# circuit.net
KiCad netlist of a schematic drawn in EAGLE
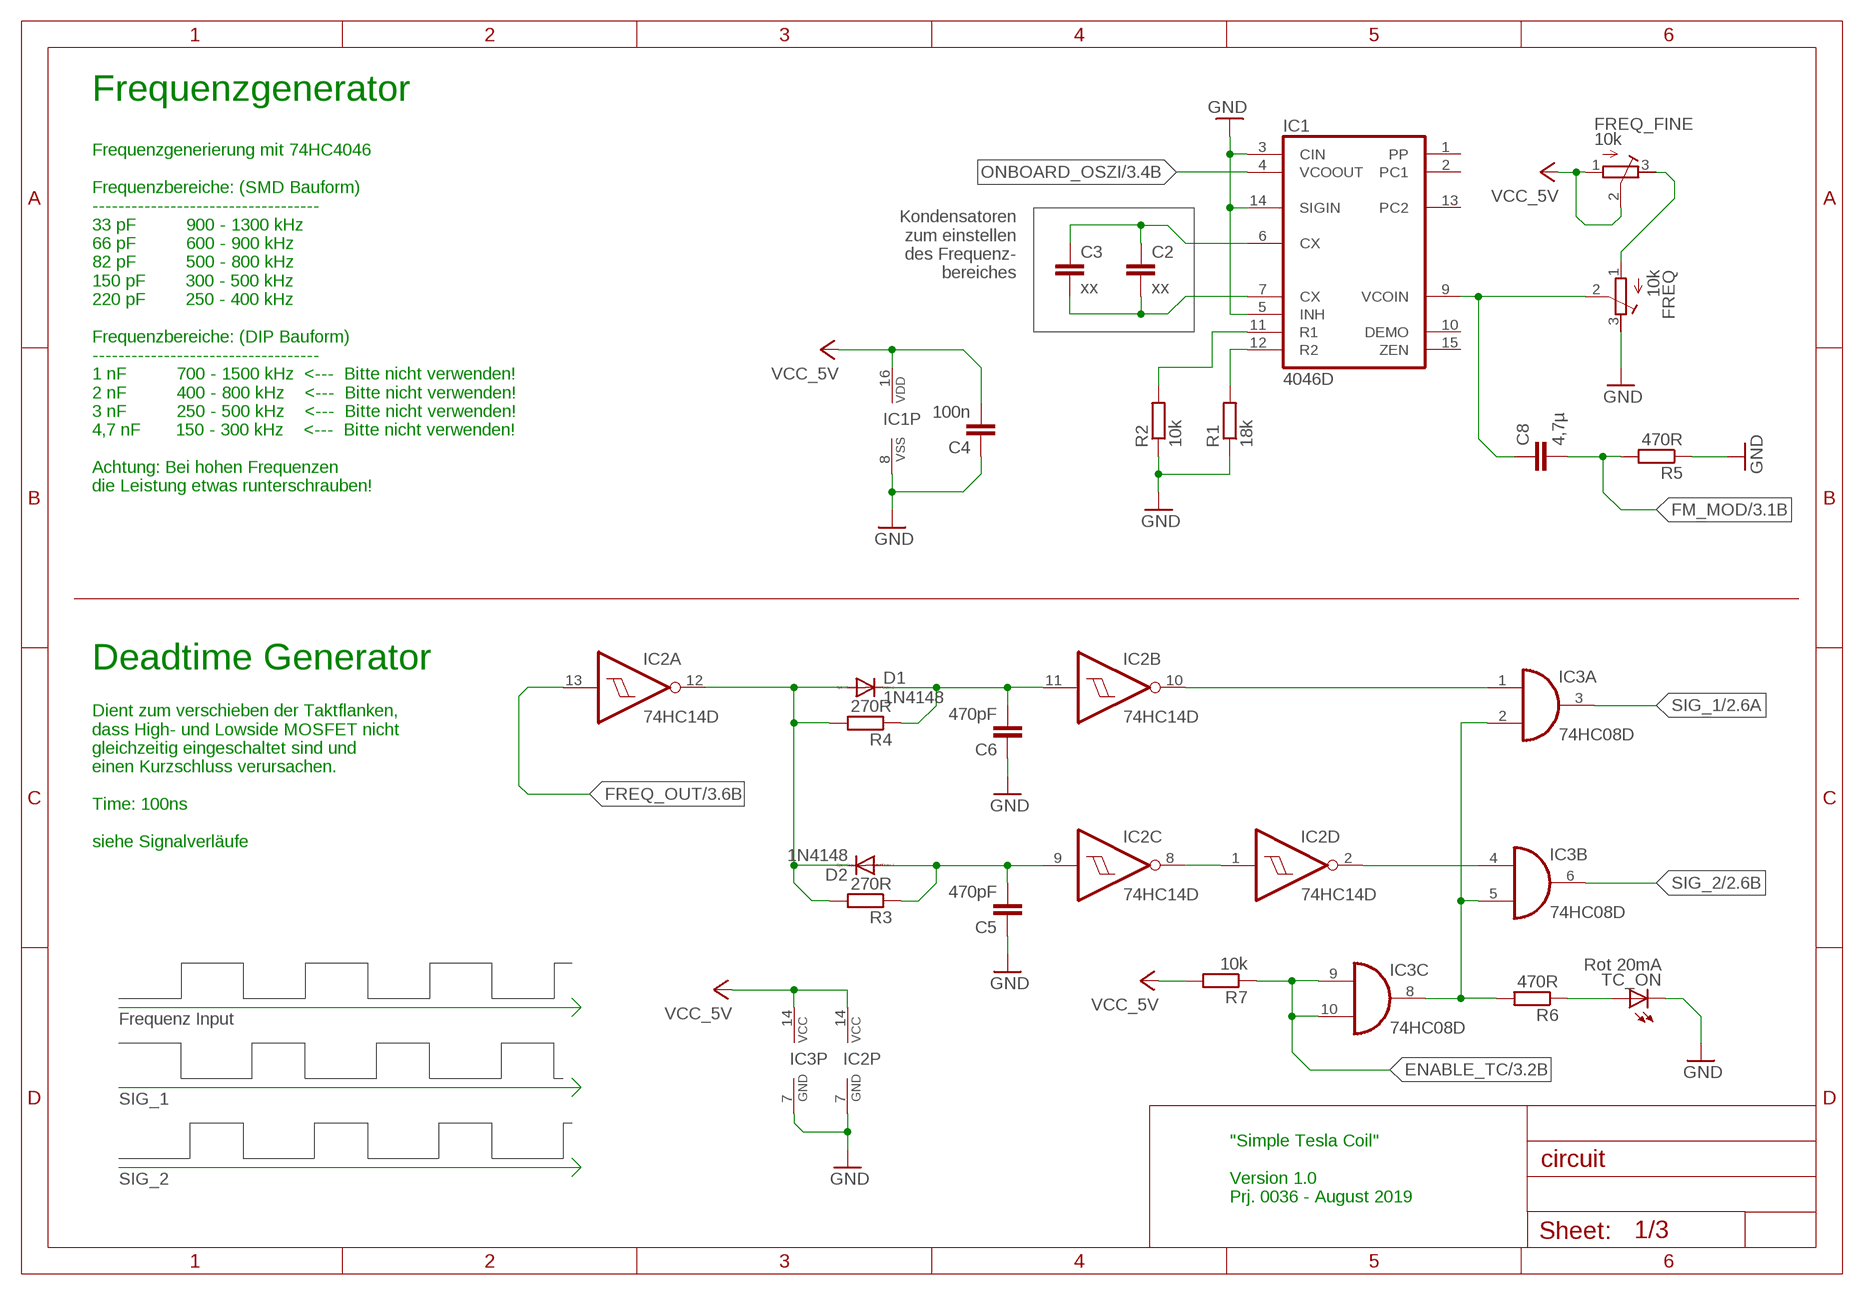
[diagram p0: schematic, sheet 1]
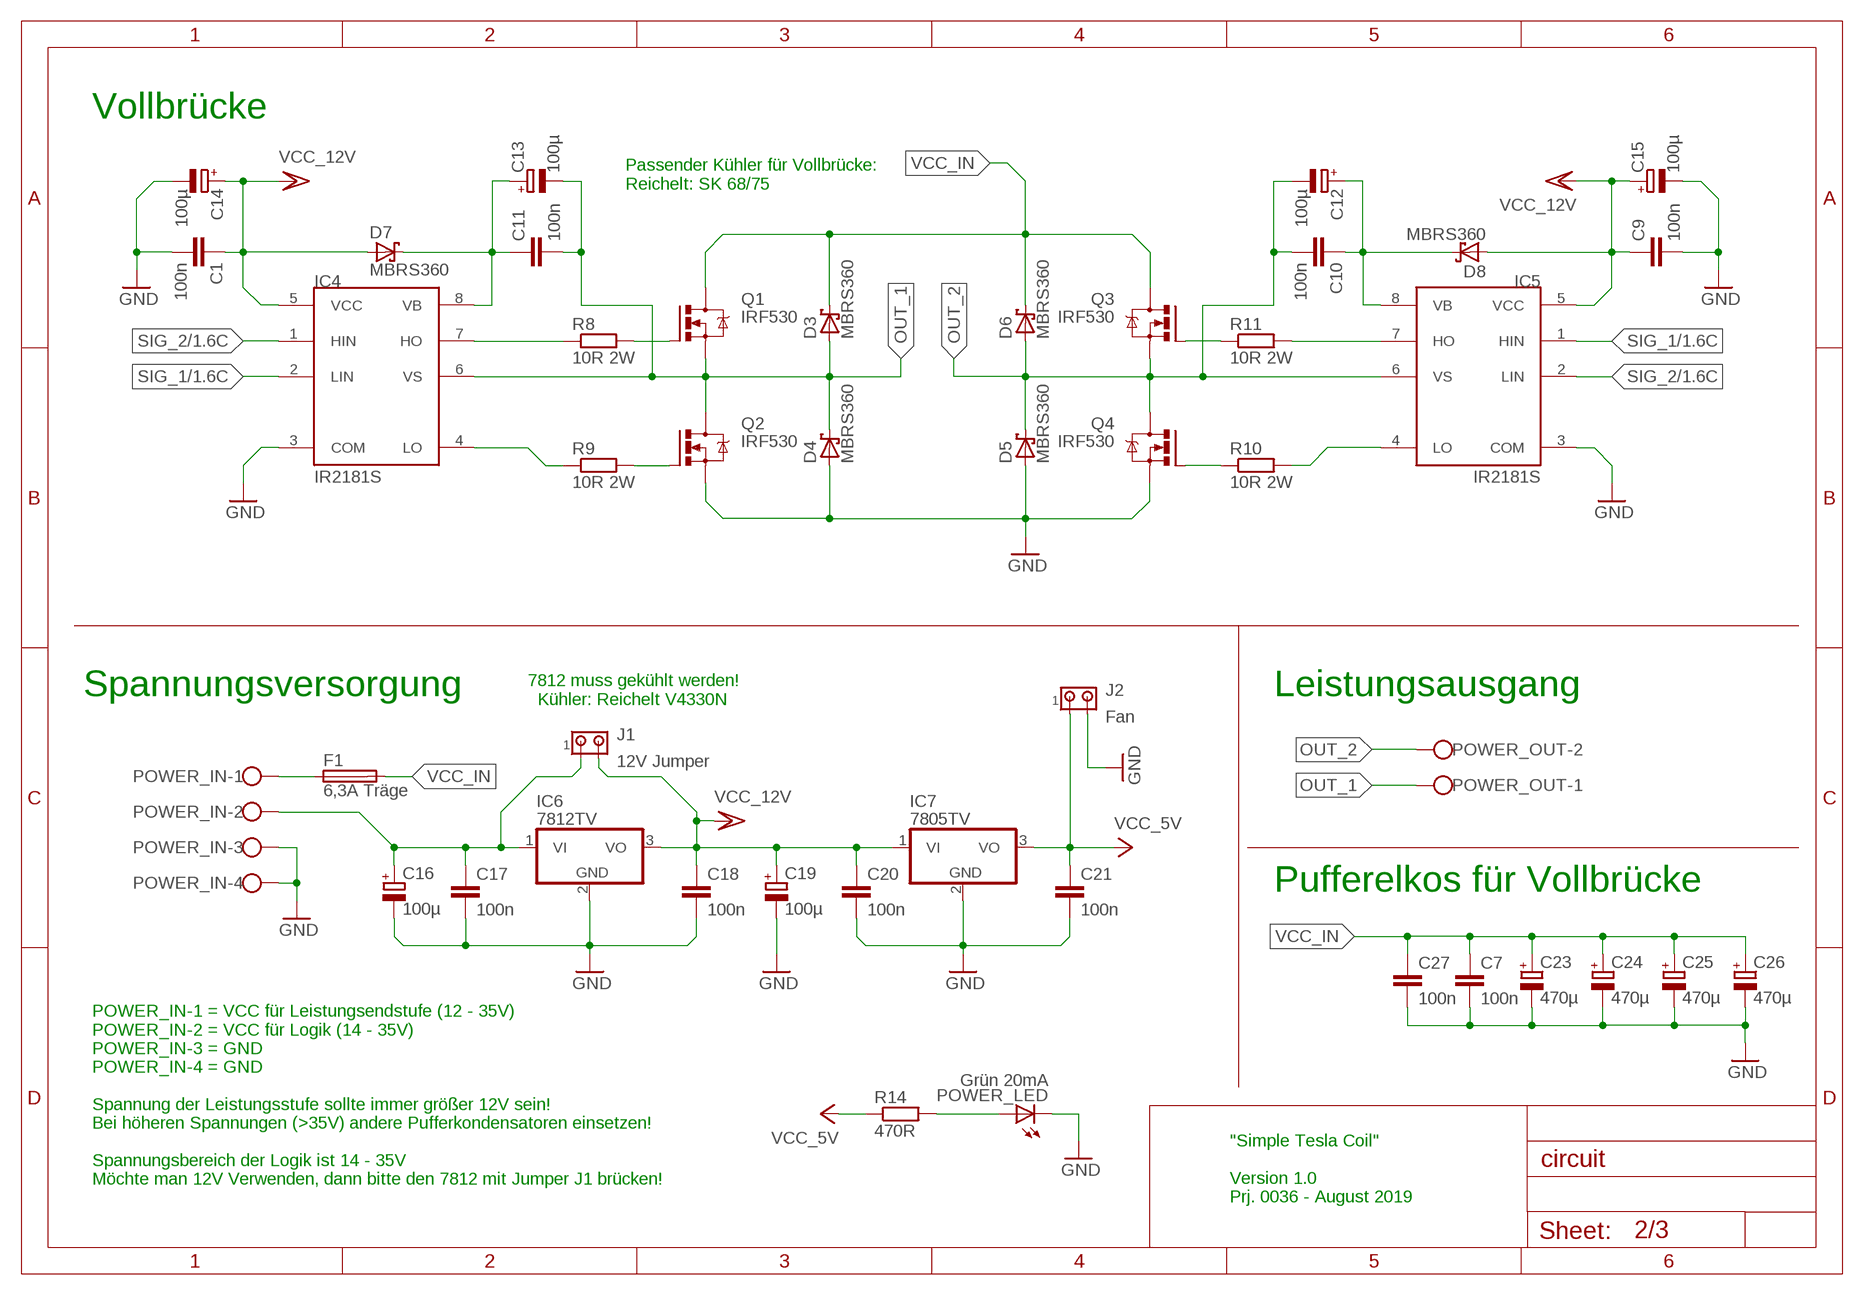
[diagram p1: schematic, sheet 2]
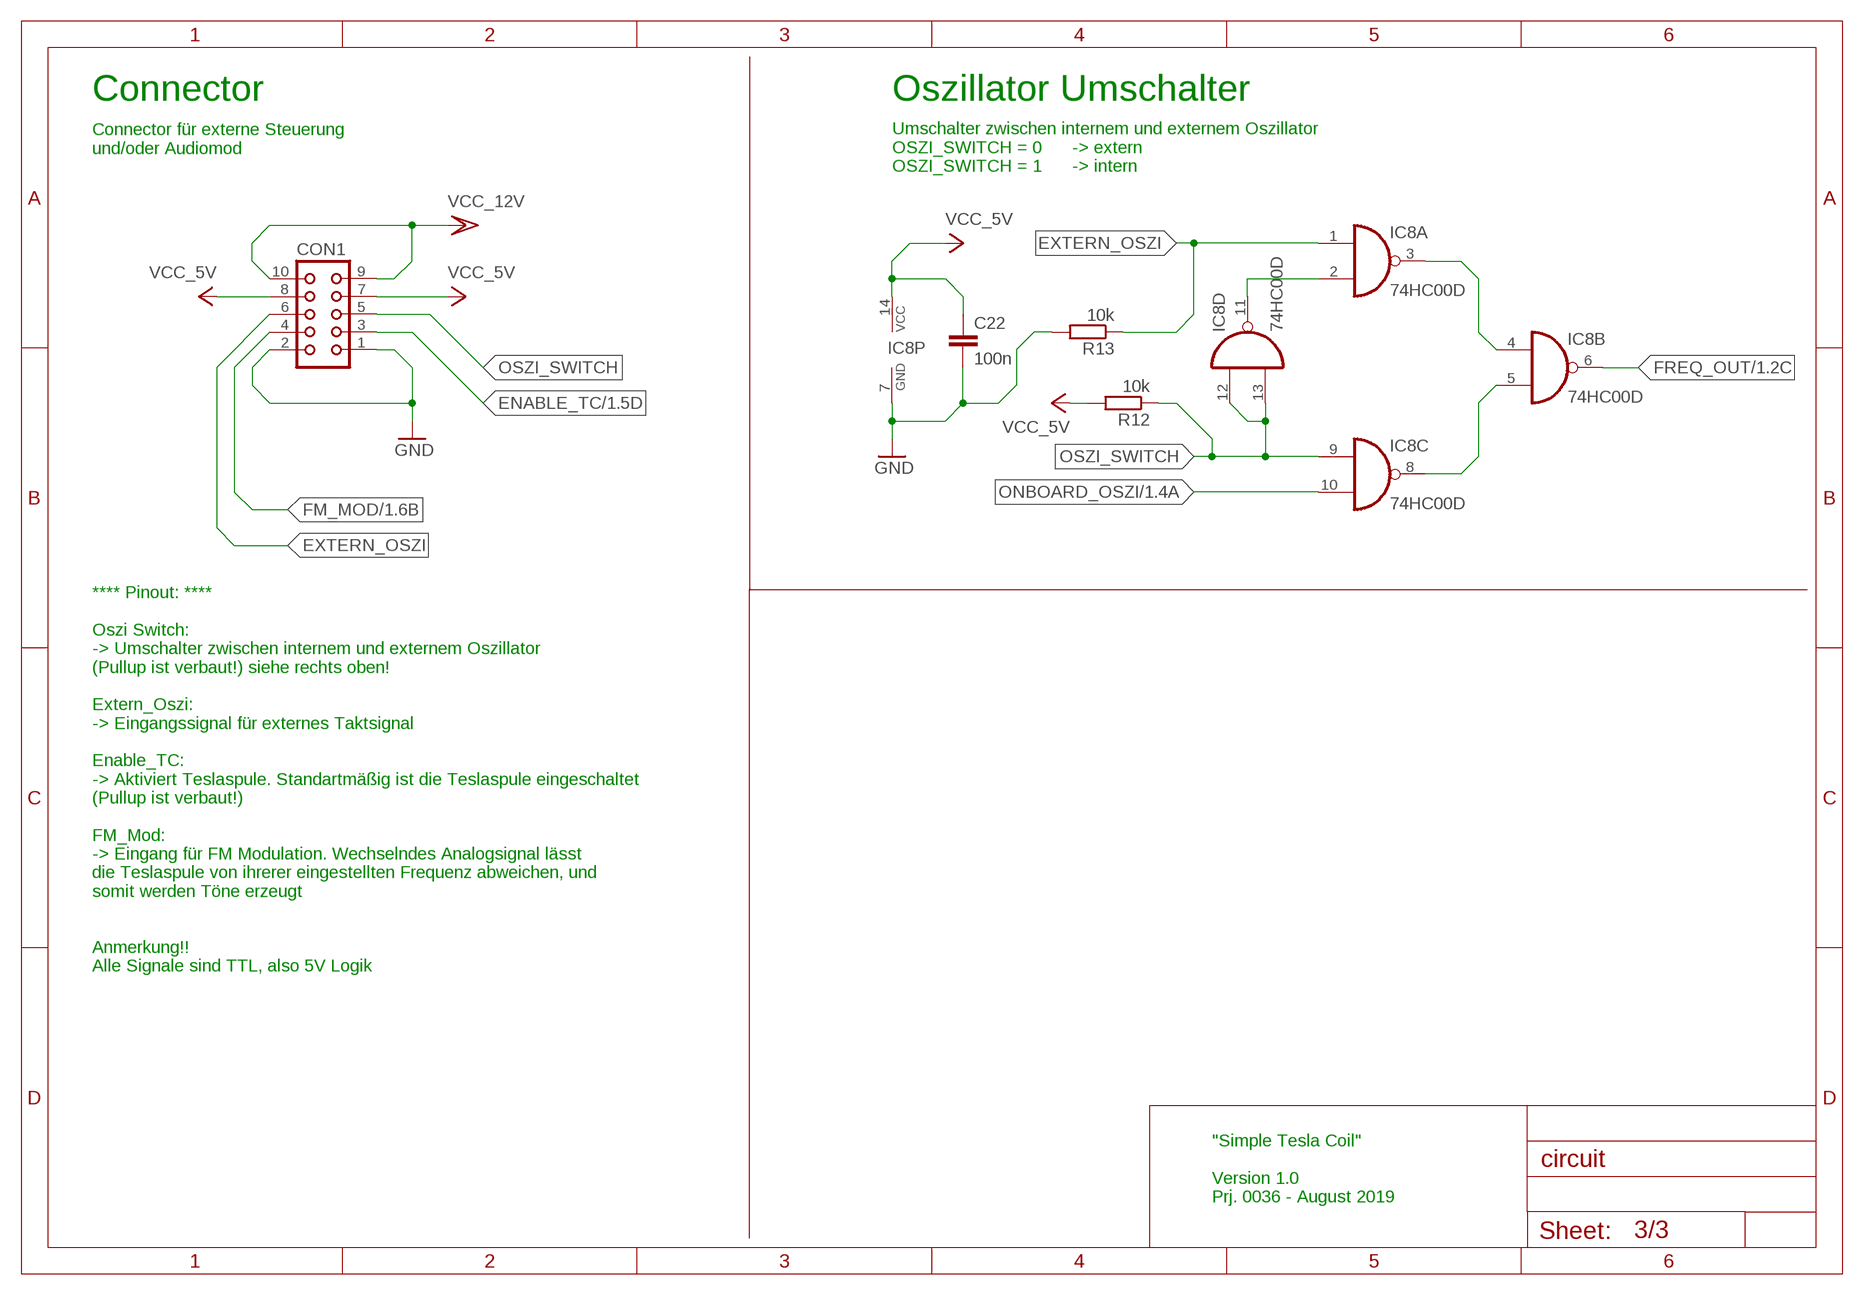
[diagram p2: schematic, sheet 3]

(export (version "E")
  (design (tool "Eeschema 10.0.6"))
  (components
    (comp (ref "C1")
      (value "100n")
      (footprint "eagle-import:C1206K")
      (libsource (lib "eagle-import") (part "C-EUC1206K"))
    )
    (comp (ref "C7")
      (value "100n")
      (footprint "eagle-import:C1206K")
      (libsource (lib "eagle-import") (part "C-EUC1206K"))
    )
    (comp (ref "C9")
      (value "100n")
      (footprint "eagle-import:C1206K")
      (libsource (lib "eagle-import") (part "C-EUC1206K"))
    )
    (comp (ref "C10")
      (value "100n")
      (footprint "eagle-import:C1206K")
      (libsource (lib "eagle-import") (part "C-EUC1206K"))
    )
    (comp (ref "C11")
      (value "100n")
      (footprint "eagle-import:C1206K")
      (libsource (lib "eagle-import") (part "C-EUC1206K"))
    )
    (comp (ref "C12")
      (value "100µ")
      (footprint "eagle-import:E2,5-7")
      (libsource (lib "eagle-import") (part "CPOL-EUE2.5-7"))
    )
    (comp (ref "C13")
      (value "100µ")
      (footprint "eagle-import:E2,5-7")
      (libsource (lib "eagle-import") (part "CPOL-EUE2.5-7"))
    )
    (comp (ref "C14")
      (value "100µ")
      (footprint "eagle-import:E2,5-7")
      (libsource (lib "eagle-import") (part "CPOL-EUE2.5-7"))
    )
    (comp (ref "C15")
      (value "100µ")
      (footprint "eagle-import:E2,5-7")
      (libsource (lib "eagle-import") (part "CPOL-EUE2.5-7"))
    )
    (comp (ref "C16")
      (value "100µ")
      (footprint "eagle-import:E2,5-7")
      (libsource (lib "eagle-import") (part "CPOL-EUE2.5-7"))
    )
    (comp (ref "C17")
      (value "100n")
      (footprint "eagle-import:C1206K")
      (libsource (lib "eagle-import") (part "C-EUC1206K"))
    )
    (comp (ref "C18")
      (value "100n")
      (footprint "eagle-import:C1206K")
      (libsource (lib "eagle-import") (part "C-EUC1206K"))
    )
    (comp (ref "C19")
      (value "100µ")
      (footprint "eagle-import:E2,5-7")
      (libsource (lib "eagle-import") (part "CPOL-EUE2.5-7"))
    )
    (comp (ref "C20")
      (value "100n")
      (footprint "eagle-import:C1206K")
      (libsource (lib "eagle-import") (part "C-EUC1206K"))
    )
    (comp (ref "C21")
      (value "100n")
      (footprint "eagle-import:C1206K")
      (libsource (lib "eagle-import") (part "C-EUC1206K"))
    )
    (comp (ref "C23")
      (value "470µ")
      (footprint "eagle-import:E5-10,5")
      (libsource (lib "eagle-import") (part "CPOL-EUE5-10.5"))
    )
    (comp (ref "C24")
      (value "470µ")
      (footprint "eagle-import:E5-10,5")
      (libsource (lib "eagle-import") (part "CPOL-EUE5-10.5"))
    )
    (comp (ref "C25")
      (value "470µ")
      (footprint "eagle-import:E5-10,5")
      (libsource (lib "eagle-import") (part "CPOL-EUE5-10.5"))
    )
    (comp (ref "C26")
      (value "470µ")
      (footprint "eagle-import:E5-10,5")
      (libsource (lib "eagle-import") (part "CPOL-EUE5-10.5"))
    )
    (comp (ref "C27")
      (value "100n")
      (footprint "eagle-import:C1206K")
      (libsource (lib "eagle-import") (part "C-EUC1206K"))
    )
    (comp (ref "D3")
      (value "MBRS360")
      (footprint "eagle-import:SMC")
      (libsource (lib "eagle-import") (part "MBRS30T34"))
    )
    (comp (ref "D4")
      (value "MBRS360")
      (footprint "eagle-import:SMC")
      (libsource (lib "eagle-import") (part "MBRS30T34"))
    )
    (comp (ref "D5")
      (value "MBRS360")
      (footprint "eagle-import:SMC")
      (libsource (lib "eagle-import") (part "MBRS30T34"))
    )
    (comp (ref "D6")
      (value "MBRS360")
      (footprint "eagle-import:SMC")
      (libsource (lib "eagle-import") (part "MBRS30T34"))
    )
    (comp (ref "D7")
      (value "MBRS360")
      (footprint "eagle-import:SMC")
      (libsource (lib "eagle-import") (part "MBRS30T34"))
    )
    (comp (ref "D8")
      (value "MBRS360")
      (footprint "eagle-import:SMC")
      (libsource (lib "eagle-import") (part "MBRS30T34"))
    )
    (comp (ref "F1")
      (value "6,3A Träge")
      (footprint "eagle-import:SH22,5")
      (fields (field (name "MF") "SCHURTER") (field (name "MPN") "0031.8201"))
      (libsource (lib "eagle-import") (part "SH22,5"))
    )
    (comp (ref "IC4")
      (value "IR2181S")
      (footprint "eagle-import:SO08")
      (libsource (lib "eagle-import") (part "IR2181S"))
    )
    (comp (ref "IC5")
      (value "IR2181S")
      (footprint "eagle-import:SO08")
      (libsource (lib "eagle-import") (part "IR2181S"))
    )
    (comp (ref "IC6")
      (value "7812TV")
      (footprint "eagle-import:TO220V")
      (libsource (lib "eagle-import") (part "78TV12"))
    )
    (comp (ref "IC7")
      (value "7805TV")
      (footprint "eagle-import:TO220V")
      (libsource (lib "eagle-import") (part "78TV05"))
    )
    (comp (ref "J1")
      (value "12V Jumper")
      (footprint "eagle-import:10X02MTA")
      (libsource (lib "eagle-import") (part "MTA02-100"))
    )
    (comp (ref "J2")
      (value "Fan")
      (footprint "eagle-import:10X02MTA")
      (libsource (lib "eagle-import") (part "MTA02-100"))
    )
    (comp (ref "POWER_IN")
      (value "W237-4")
      (footprint "eagle-import:W237-4")
      (libsource (lib "eagle-import") (part "W237-4"))
    )
    (comp (ref "POWER_LED")
      (value "Grün 20mA")
      (footprint "eagle-import:1206")
      (libsource (lib "eagle-import") (part "LEDSMT1206"))
    )
    (comp (ref "POWER_OUT")
      (value "W237-102")
      (footprint "eagle-import:W237-102")
      (fields (field (name "MPN") "237-102"))
      (libsource (lib "eagle-import") (part "W237-102"))
    )
    (comp (ref "Q1")
      (value "IRF530")
      (footprint "eagle-import:TO220BV")
      (libsource (lib "eagle-import") (part "IRF530"))
    )
    (comp (ref "Q2")
      (value "IRF530")
      (footprint "eagle-import:TO220BV")
      (libsource (lib "eagle-import") (part "IRF530"))
    )
    (comp (ref "Q3")
      (value "IRF530")
      (footprint "eagle-import:TO220BV")
      (libsource (lib "eagle-import") (part "IRF530"))
    )
    (comp (ref "Q4")
      (value "IRF530")
      (footprint "eagle-import:TO220BV")
      (libsource (lib "eagle-import") (part "IRF530"))
    )
    (comp (ref "R8")
      (value "10R 2W")
      (footprint "eagle-import:0411_15")
      (libsource (lib "eagle-import") (part "R-EU_0411/15"))
    )
    (comp (ref "R9")
      (value "10R 2W")
      (footprint "eagle-import:0411_15")
      (libsource (lib "eagle-import") (part "R-EU_0411/15"))
    )
    (comp (ref "R10")
      (value "10R 2W")
      (footprint "eagle-import:0411_15")
      (libsource (lib "eagle-import") (part "R-EU_0411/15"))
    )
    (comp (ref "R11")
      (value "10R 2W")
      (footprint "eagle-import:0411_15")
      (libsource (lib "eagle-import") (part "R-EU_0411/15"))
    )
    (comp (ref "R14")
      (value "470R")
      (footprint "eagle-import:M1206")
      (libsource (lib "eagle-import") (part "R-EU_M1206"))
    )
    (comp (ref "C22")
      (value "100n")
      (footprint "eagle-import:C1206K")
      (libsource (lib "eagle-import") (part "C-EUC1206K"))
    )
    (comp (ref "CON1")
      (value "CON10")
      (footprint "eagle-import:CON10")
      (libsource (lib "eagle-import") (part "CON10"))
    )
    (comp (ref "IC8")
      (value "74HC00D")
      (footprint "eagle-import:SO14")
      (libsource (lib "eagle-import") (part "7400DHC"))
    )
    (comp (ref "R12")
      (value "10k")
      (footprint "eagle-import:M1206")
      (libsource (lib "eagle-import") (part "R-EU_M1206"))
    )
    (comp (ref "R13")
      (value "10k")
      (footprint "eagle-import:M1206")
      (libsource (lib "eagle-import") (part "R-EU_M1206"))
    )
    (comp (ref "C2")
      (value "xx")
      (footprint "eagle-import:C0805K")
      (libsource (lib "eagle-import") (part "C-EUC0805K"))
    )
    (comp (ref "C3")
      (value "xx")
      (footprint "eagle-import:C0805K")
      (libsource (lib "eagle-import") (part "C-EUC0805K"))
    )
    (comp (ref "C4")
      (value "100n")
      (footprint "eagle-import:C1206K")
      (libsource (lib "eagle-import") (part "C-EUC1206K"))
    )
    (comp (ref "C5")
      (value "470pF")
      (footprint "eagle-import:C1206K")
      (libsource (lib "eagle-import") (part "C-EUC1206K"))
    )
    (comp (ref "C6")
      (value "470pF")
      (footprint "eagle-import:C1206K")
      (libsource (lib "eagle-import") (part "C-EUC1206K"))
    )
    (comp (ref "C8")
      (value "4,7µ")
      (footprint "eagle-import:C1206K")
      (libsource (lib "eagle-import") (part "C-EUC1206K"))
    )
    (comp (ref "D1")
      (value "1N4148")
      (footprint "eagle-import:SOD323-W")
      (libsource (lib "eagle-import") (part "DIODE-SOD323-W"))
    )
    (comp (ref "D2")
      (value "1N4148")
      (footprint "eagle-import:SOD323-W")
      (libsource (lib "eagle-import") (part "DIODE-SOD323-W"))
    )
    (comp (ref "FREQ")
      (value "10k")
      (footprint "eagle-import:RTRIM64W")
      (libsource (lib "eagle-import") (part "R-TRIMM64W"))
    )
    (comp (ref "FREQ_FINE")
      (value "10k")
      (footprint "eagle-import:RTRIM64W")
      (libsource (lib "eagle-import") (part "R-TRIMM64W"))
    )
    (comp (ref "IC1")
      (value "4046D")
      (footprint "eagle-import:SO16")
      (libsource (lib "eagle-import") (part "4046D"))
    )
    (comp (ref "IC2")
      (value "74HC14D")
      (footprint "eagle-import:SO14")
      (libsource (lib "eagle-import") (part "7414DHCT"))
    )
    (comp (ref "IC3")
      (value "74HC08D")
      (footprint "eagle-import:SO14")
      (libsource (lib "eagle-import") (part "7408DHC"))
    )
    (comp (ref "R1")
      (value "18k")
      (footprint "eagle-import:M1206")
      (libsource (lib "eagle-import") (part "R-EU_M1206"))
    )
    (comp (ref "R2")
      (value "10k")
      (footprint "eagle-import:M1206")
      (libsource (lib "eagle-import") (part "R-EU_M1206"))
    )
    (comp (ref "R3")
      (value "270R")
      (footprint "eagle-import:M1206")
      (libsource (lib "eagle-import") (part "R-EU_M1206"))
    )
    (comp (ref "R4")
      (value "270R")
      (footprint "eagle-import:M1206")
      (libsource (lib "eagle-import") (part "R-EU_M1206"))
    )
    (comp (ref "R5")
      (value "470R")
      (footprint "eagle-import:M1206")
      (libsource (lib "eagle-import") (part "R-EU_M1206"))
    )
    (comp (ref "R6")
      (value "470R")
      (footprint "eagle-import:M1206")
      (libsource (lib "eagle-import") (part "R-EU_M1206"))
    )
    (comp (ref "R7")
      (value "10k")
      (footprint "eagle-import:M1206")
      (libsource (lib "eagle-import") (part "R-EU_M1206"))
    )
    (comp (ref "TC_ON")
      (value "Rot 20mA")
      (footprint "eagle-import:1206")
      (libsource (lib "eagle-import") (part "LEDSMT1206"))
    )
  )
  (nets
    (net (code "1") (name "ENABLE_TC") (class "Default")
      (node (ref "CON1") (pin "3") (pinfunction "3_3") (pintype "passive"))
      (node (ref "IC3") (pin "10") (pinfunction "I1_10") (pintype "input"))
      (node (ref "IC3") (pin "9") (pinfunction "I0_9") (pintype "input"))
      (node (ref "R7") (pin "1") (pinfunction "1_1") (pintype "passive"))
    )
    (net (code "2") (name "EXTERN_OSZI") (class "Default")
      (node (ref "CON1") (pin "6") (pinfunction "6_6") (pintype "passive"))
      (node (ref "IC8") (pin "1") (pinfunction "I0_1") (pintype "input"))
      (node (ref "R13") (pin "1") (pinfunction "1_1") (pintype "passive"))
    )
    (net (code "3") (name "FM_MOD") (class "Default")
      (node (ref "C8") (pin "2") (pinfunction "2_2") (pintype "passive"))
      (node (ref "CON1") (pin "4") (pinfunction "4_4") (pintype "passive"))
      (node (ref "R5") (pin "2") (pinfunction "2_2") (pintype "passive"))
    )
    (net (code "4") (name "FREQ_OUT") (class "Default")
      (node (ref "IC2") (pin "13") (pinfunction "I_13") (pintype "input"))
      (node (ref "IC8") (pin "6") (pinfunction "O_6") (pintype "output"))
    )
    (net (code "5") (name "GND") (class "Default")
      (node (ref "C1") (pin "2") (pinfunction "2_2") (pintype "passive"))
      (node (ref "C14") (pin "-") (pinfunction "-_-") (pintype "passive"))
      (node (ref "C15") (pin "-") (pinfunction "-_-") (pintype "passive"))
      (node (ref "C16") (pin "-") (pinfunction "-_-") (pintype "passive"))
      (node (ref "C17") (pin "2") (pinfunction "2_2") (pintype "passive"))
      (node (ref "C18") (pin "2") (pinfunction "2_2") (pintype "passive"))
      (node (ref "C19") (pin "-") (pinfunction "-_-") (pintype "passive"))
      (node (ref "C20") (pin "2") (pinfunction "2_2") (pintype "passive"))
      (node (ref "C21") (pin "2") (pinfunction "2_2") (pintype "passive"))
      (node (ref "C22") (pin "2") (pinfunction "2_2") (pintype "passive"))
      (node (ref "C23") (pin "-") (pinfunction "-_-") (pintype "passive"))
      (node (ref "C24") (pin "-") (pinfunction "-_-") (pintype "passive"))
      (node (ref "C25") (pin "-") (pinfunction "-_-") (pintype "passive"))
      (node (ref "C26") (pin "-") (pinfunction "-_-") (pintype "passive"))
      (node (ref "C27") (pin "2") (pinfunction "2_2") (pintype "passive"))
      (node (ref "C4") (pin "1") (pinfunction "1_1") (pintype "passive"))
      (node (ref "C5") (pin "1") (pinfunction "1_1") (pintype "passive"))
      (node (ref "C6") (pin "1") (pinfunction "1_1") (pintype "passive"))
      (node (ref "C7") (pin "2") (pinfunction "2_2") (pintype "passive"))
      (node (ref "C9") (pin "2") (pinfunction "2_2") (pintype "passive"))
      (node (ref "CON1") (pin "1") (pinfunction "1_1") (pintype "passive"))
      (node (ref "CON1") (pin "2") (pinfunction "2_2") (pintype "passive"))
      (node (ref "D4") (pin "A") (pinfunction "A_A") (pintype "passive"))
      (node (ref "D5") (pin "A") (pinfunction "A_A") (pintype "passive"))
      (node (ref "FREQ") (pin "3") (pinfunction "E_3") (pintype "passive"))
      (node (ref "IC1") (pin "14") (pinfunction "SIGIN_14") (pintype "input"))
      (node (ref "IC1") (pin "3") (pinfunction "CIN_3") (pintype "input"))
      (node (ref "IC1") (pin "5") (pinfunction "INH_5") (pintype "input"))
      (node (ref "IC1") (pin "8") (pinfunction "VSS_8") (pintype "power_in"))
      (node (ref "IC2") (pin "7") (pinfunction "GND_7") (pintype "power_in"))
      (node (ref "IC3") (pin "7") (pinfunction "GND_7") (pintype "power_in"))
      (node (ref "IC4") (pin "3") (pinfunction "COM_3") (pintype "power_in"))
      (node (ref "IC5") (pin "3") (pinfunction "COM_3") (pintype "power_in"))
      (node (ref "IC6") (pin "2") (pinfunction "GND_2") (pintype "passive"))
      (node (ref "IC7") (pin "2") (pinfunction "GND_2") (pintype "passive"))
      (node (ref "IC8") (pin "7") (pinfunction "GND_7") (pintype "power_in"))
      (node (ref "J2") (pin "2") (pinfunction "2_2") (pintype "passive"))
      (node (ref "POWER_IN") (pin "3") (pinfunction "KL_3") (pintype "passive"))
      (node (ref "POWER_IN") (pin "4") (pinfunction "KL_4") (pintype "passive"))
      (node (ref "POWER_LED") (pin "C") (pinfunction "C_C") (pintype "passive"))
      (node (ref "Q2") (pin "S") (pinfunction "S_S") (pintype "passive"))
      (node (ref "Q4") (pin "S") (pinfunction "S_S") (pintype "passive"))
      (node (ref "R1") (pin "1") (pinfunction "1_1") (pintype "passive"))
      (node (ref "R13") (pin "2") (pinfunction "2_2") (pintype "passive"))
      (node (ref "R2") (pin "1") (pinfunction "1_1") (pintype "passive"))
      (node (ref "R5") (pin "1") (pinfunction "1_1") (pintype "passive"))
      (node (ref "TC_ON") (pin "C") (pinfunction "C_C") (pintype "passive"))
    )
    (net (code "6") (name "Net-(C2-Pad1)") (class "Default")
      (node (ref "C2") (pin "1") (pinfunction "1_1") (pintype "passive"))
      (node (ref "C3") (pin "1") (pinfunction "1_1") (pintype "passive"))
      (node (ref "IC1") (pin "6") (pinfunction "CX_6") (pintype "input"))
    )
    (net (code "7") (name "Net-(C2-Pad2)") (class "Default")
      (node (ref "C2") (pin "2") (pinfunction "2_2") (pintype "passive"))
      (node (ref "C3") (pin "2") (pinfunction "2_2") (pintype "passive"))
      (node (ref "IC1") (pin "7") (pinfunction "CX_7") (pintype "input"))
    )
    (net (code "8") (name "Net-(FREQ-A)") (class "Default")
      (node (ref "FREQ") (pin "1") (pinfunction "A_1") (pintype "passive"))
      (node (ref "FREQ_FINE") (pin "3") (pinfunction "E_3") (pintype "passive"))
    )
    (net (code "9") (name "Net-(FREQ-S)") (class "Default")
      (node (ref "C8") (pin "1") (pinfunction "1_1") (pintype "passive"))
      (node (ref "FREQ") (pin "2") (pinfunction "S_2") (pintype "passive"))
      (node (ref "IC1") (pin "9") (pinfunction "VCOIN_9") (pintype "input"))
    )
    (net (code "10") (name "Net-(IC1A-R1)") (class "Default")
      (node (ref "IC1") (pin "11") (pinfunction "R1_11") (pintype "input"))
      (node (ref "R2") (pin "2") (pinfunction "2_2") (pintype "passive"))
    )
    (net (code "11") (name "Net-(IC1A-R2)") (class "Default")
      (node (ref "IC1") (pin "12") (pinfunction "R2_12") (pintype "input"))
      (node (ref "R1") (pin "2") (pinfunction "2_2") (pintype "passive"))
    )
    (net (code "12") (name "Net-(IC2A-O)") (class "Default")
      (node (ref "D1") (pin "A") (pinfunction "A_A") (pintype "passive"))
      (node (ref "D2") (pin "C") (pinfunction "C_C") (pintype "passive"))
      (node (ref "IC2") (pin "12") (pinfunction "O_12") (pintype "output"))
      (node (ref "R3") (pin "2") (pinfunction "2_2") (pintype "passive"))
      (node (ref "R4") (pin "2") (pinfunction "2_2") (pintype "passive"))
    )
    (net (code "13") (name "Net-(IC2B-I)") (class "Default")
      (node (ref "C6") (pin "2") (pinfunction "2_2") (pintype "passive"))
      (node (ref "D1") (pin "C") (pinfunction "C_C") (pintype "passive"))
      (node (ref "IC2") (pin "11") (pinfunction "I_11") (pintype "input"))
      (node (ref "R4") (pin "1") (pinfunction "1_1") (pintype "passive"))
    )
    (net (code "14") (name "Net-(IC2B-O)") (class "Default")
      (node (ref "IC2") (pin "10") (pinfunction "O_10") (pintype "output"))
      (node (ref "IC3") (pin "1") (pinfunction "I0_1") (pintype "input"))
    )
    (net (code "15") (name "Net-(IC2C-I)") (class "Default")
      (node (ref "C5") (pin "2") (pinfunction "2_2") (pintype "passive"))
      (node (ref "D2") (pin "A") (pinfunction "A_A") (pintype "passive"))
      (node (ref "IC2") (pin "9") (pinfunction "I_9") (pintype "input"))
      (node (ref "R3") (pin "1") (pinfunction "1_1") (pintype "passive"))
    )
    (net (code "16") (name "Net-(IC2C-O)") (class "Default")
      (node (ref "IC2") (pin "1") (pinfunction "I_1") (pintype "input"))
      (node (ref "IC2") (pin "8") (pinfunction "O_8") (pintype "output"))
    )
    (net (code "17") (name "Net-(IC2D-O)") (class "Default")
      (node (ref "IC2") (pin "2") (pinfunction "O_2") (pintype "output"))
      (node (ref "IC3") (pin "4") (pinfunction "I0_4") (pintype "input"))
    )
    (net (code "18") (name "Net-(IC3A-I1)") (class "Default")
      (node (ref "IC3") (pin "2") (pinfunction "I1_2") (pintype "input"))
      (node (ref "IC3") (pin "5") (pinfunction "I1_5") (pintype "input"))
      (node (ref "IC3") (pin "8") (pinfunction "O_8") (pintype "output"))
      (node (ref "R6") (pin "2") (pinfunction "2_2") (pintype "passive"))
    )
    (net (code "19") (name "Net-(IC4-HO)") (class "Default")
      (node (ref "IC4") (pin "7") (pinfunction "HO_7") (pintype "output"))
      (node (ref "R8") (pin "1") (pinfunction "1_1") (pintype "passive"))
    )
    (net (code "20") (name "Net-(IC4-LO)") (class "Default")
      (node (ref "IC4") (pin "4") (pinfunction "LO_4") (pintype "output"))
      (node (ref "R9") (pin "1") (pinfunction "1_1") (pintype "passive"))
    )
    (net (code "21") (name "Net-(IC4-VB)") (class "Default")
      (node (ref "C11") (pin "1") (pinfunction "1_1") (pintype "passive"))
      (node (ref "C13") (pin "+") (pinfunction "+_+") (pintype "passive"))
      (node (ref "D7") (pin "C") (pinfunction "C_C") (pintype "passive"))
      (node (ref "IC4") (pin "8") (pinfunction "VB_8") (pintype "power_in"))
    )
    (net (code "22") (name "Net-(IC5-HO)") (class "Default")
      (node (ref "IC5") (pin "7") (pinfunction "HO_7") (pintype "output"))
      (node (ref "R11") (pin "2") (pinfunction "2_2") (pintype "passive"))
    )
    (net (code "23") (name "Net-(IC5-LO)") (class "Default")
      (node (ref "IC5") (pin "4") (pinfunction "LO_4") (pintype "output"))
      (node (ref "R10") (pin "2") (pinfunction "2_2") (pintype "passive"))
    )
    (net (code "24") (name "Net-(IC5-VB)") (class "Default")
      (node (ref "C10") (pin "1") (pinfunction "1_1") (pintype "passive"))
      (node (ref "C12") (pin "+") (pinfunction "+_+") (pintype "passive"))
      (node (ref "D8") (pin "C") (pinfunction "C_C") (pintype "passive"))
      (node (ref "IC5") (pin "8") (pinfunction "VB_8") (pintype "power_in"))
    )
    (net (code "25") (name "Net-(IC6-VI)") (class "Default")
      (node (ref "C16") (pin "+") (pinfunction "+_+") (pintype "passive"))
      (node (ref "C17") (pin "1") (pinfunction "1_1") (pintype "passive"))
      (node (ref "IC6") (pin "1") (pinfunction "VI_1") (pintype "input"))
      (node (ref "J1") (pin "1") (pinfunction "1_1") (pintype "passive"))
      (node (ref "POWER_IN") (pin "2") (pinfunction "KL_2") (pintype "passive"))
    )
    (net (code "26") (name "Net-(IC8A-I1)") (class "Default")
      (node (ref "IC8") (pin "11") (pinfunction "O_11") (pintype "output"))
      (node (ref "IC8") (pin "2") (pinfunction "I1_2") (pintype "input"))
    )
    (net (code "27") (name "Net-(IC8A-O)") (class "Default")
      (node (ref "IC8") (pin "3") (pinfunction "O_3") (pintype "output"))
      (node (ref "IC8") (pin "4") (pinfunction "I0_4") (pintype "input"))
    )
    (net (code "28") (name "Net-(IC8B-I1)") (class "Default")
      (node (ref "IC8") (pin "5") (pinfunction "I1_5") (pintype "input"))
      (node (ref "IC8") (pin "8") (pinfunction "O_8") (pintype "output"))
    )
    (net (code "29") (name "Net-(POWER_INA-KL)") (class "Default")
      (node (ref "F1") (pin "1") (pinfunction "1_1") (pintype "passive"))
      (node (ref "POWER_IN") (pin "1") (pinfunction "KL_1") (pintype "passive"))
    )
    (net (code "30") (name "Net-(POWER_LED-PadA)") (class "Default")
      (node (ref "POWER_LED") (pin "A") (pinfunction "A_A") (pintype "passive"))
      (node (ref "R14") (pin "2") (pinfunction "2_2") (pintype "passive"))
    )
    (net (code "31") (name "Net-(Q1-PadG)") (class "Default")
      (node (ref "Q1") (pin "G") (pinfunction "G_G") (pintype "passive"))
      (node (ref "R8") (pin "2") (pinfunction "2_2") (pintype "passive"))
    )
    (net (code "32") (name "Net-(Q2-PadG)") (class "Default")
      (node (ref "Q2") (pin "G") (pinfunction "G_G") (pintype "passive"))
      (node (ref "R9") (pin "2") (pinfunction "2_2") (pintype "passive"))
    )
    (net (code "33") (name "Net-(Q3-PadG)") (class "Default")
      (node (ref "Q3") (pin "G") (pinfunction "G_G") (pintype "passive"))
      (node (ref "R11") (pin "1") (pinfunction "1_1") (pintype "passive"))
    )
    (net (code "34") (name "Net-(Q4-PadG)") (class "Default")
      (node (ref "Q4") (pin "G") (pinfunction "G_G") (pintype "passive"))
      (node (ref "R10") (pin "1") (pinfunction "1_1") (pintype "passive"))
    )
    (net (code "35") (name "Net-(R6-Pad1)") (class "Default")
      (node (ref "R6") (pin "1") (pinfunction "1_1") (pintype "passive"))
      (node (ref "TC_ON") (pin "A") (pinfunction "A_A") (pintype "passive"))
    )
    (net (code "36") (name "ONBOARD_OSZI") (class "Default")
      (node (ref "IC1") (pin "4") (pinfunction "VCOOUT_4") (pintype "output"))
      (node (ref "IC8") (pin "10") (pinfunction "I1_10") (pintype "input"))
    )
    (net (code "37") (name "OSZI_SWITCH") (class "Default")
      (node (ref "CON1") (pin "5") (pinfunction "5_5") (pintype "passive"))
      (node (ref "IC8") (pin "12") (pinfunction "I0_12") (pintype "input"))
      (node (ref "IC8") (pin "13") (pinfunction "I1_13") (pintype "input"))
      (node (ref "IC8") (pin "9") (pinfunction "I0_9") (pintype "input"))
      (node (ref "R12") (pin "1") (pinfunction "1_1") (pintype "passive"))
    )
    (net (code "38") (name "OUT_1") (class "Default")
      (node (ref "C11") (pin "2") (pinfunction "2_2") (pintype "passive"))
      (node (ref "C13") (pin "-") (pinfunction "-_-") (pintype "passive"))
      (node (ref "D3") (pin "A") (pinfunction "A_A") (pintype "passive"))
      (node (ref "D4") (pin "C") (pinfunction "C_C") (pintype "passive"))
      (node (ref "IC4") (pin "6") (pinfunction "VS_6") (pintype "power_in"))
      (node (ref "POWER_OUT") (pin "1") (pinfunction "KL_1") (pintype "passive"))
      (node (ref "Q1") (pin "S") (pinfunction "S_S") (pintype "passive"))
      (node (ref "Q2") (pin "D") (pinfunction "D_D") (pintype "passive"))
    )
    (net (code "39") (name "OUT_2") (class "Default")
      (node (ref "C10") (pin "2") (pinfunction "2_2") (pintype "passive"))
      (node (ref "C12") (pin "-") (pinfunction "-_-") (pintype "passive"))
      (node (ref "D5") (pin "C") (pinfunction "C_C") (pintype "passive"))
      (node (ref "D6") (pin "A") (pinfunction "A_A") (pintype "passive"))
      (node (ref "IC5") (pin "6") (pinfunction "VS_6") (pintype "power_in"))
      (node (ref "POWER_OUT") (pin "2") (pinfunction "KL_2") (pintype "passive"))
      (node (ref "Q3") (pin "S") (pinfunction "S_S") (pintype "passive"))
      (node (ref "Q4") (pin "D") (pinfunction "D_D") (pintype "passive"))
    )
    (net (code "40") (name "SIG_1") (class "Default")
      (node (ref "IC3") (pin "3") (pinfunction "O_3") (pintype "output"))
      (node (ref "IC4") (pin "2") (pinfunction "LIN_2") (pintype "input"))
      (node (ref "IC5") (pin "1") (pinfunction "HIN_1") (pintype "input"))
    )
    (net (code "41") (name "SIG_2") (class "Default")
      (node (ref "IC3") (pin "6") (pinfunction "O_6") (pintype "output"))
      (node (ref "IC4") (pin "1") (pinfunction "HIN_1") (pintype "input"))
      (node (ref "IC5") (pin "2") (pinfunction "LIN_2") (pintype "input"))
    )
    (net (code "42") (name "VCC") (class "Default")
      (node (ref "C21") (pin "1") (pinfunction "1_1") (pintype "passive"))
      (node (ref "C22") (pin "1") (pinfunction "1_1") (pintype "passive"))
      (node (ref "C4") (pin "2") (pinfunction "2_2") (pintype "passive"))
      (node (ref "CON1") (pin "7") (pinfunction "7_7") (pintype "passive"))
      (node (ref "CON1") (pin "8") (pinfunction "8_8") (pintype "passive"))
      (node (ref "FREQ_FINE") (pin "1") (pinfunction "A_1") (pintype "passive"))
      (node (ref "FREQ_FINE") (pin "2") (pinfunction "S_2") (pintype "passive"))
      (node (ref "IC1") (pin "16") (pinfunction "VDD_16") (pintype "power_in"))
      (node (ref "IC2") (pin "14") (pinfunction "VCC_14") (pintype "power_in"))
      (node (ref "IC3") (pin "14") (pinfunction "VCC_14") (pintype "power_in"))
      (node (ref "IC7") (pin "3") (pinfunction "VO_3") (pintype "passive"))
      (node (ref "IC8") (pin "14") (pinfunction "VCC_14") (pintype "power_in"))
      (node (ref "J2") (pin "1") (pinfunction "1_1") (pintype "passive"))
      (node (ref "R12") (pin "2") (pinfunction "2_2") (pintype "passive"))
      (node (ref "R14") (pin "1") (pinfunction "1_1") (pintype "passive"))
      (node (ref "R7") (pin "2") (pinfunction "2_2") (pintype "passive"))
    )
    (net (code "43") (name "VCC_IN") (class "Default")
      (node (ref "C23") (pin "+") (pinfunction "+_+") (pintype "passive"))
      (node (ref "C24") (pin "+") (pinfunction "+_+") (pintype "passive"))
      (node (ref "C25") (pin "+") (pinfunction "+_+") (pintype "passive"))
      (node (ref "C26") (pin "+") (pinfunction "+_+") (pintype "passive"))
      (node (ref "C27") (pin "1") (pinfunction "1_1") (pintype "passive"))
      (node (ref "C7") (pin "1") (pinfunction "1_1") (pintype "passive"))
      (node (ref "D3") (pin "C") (pinfunction "C_C") (pintype "passive"))
      (node (ref "D6") (pin "C") (pinfunction "C_C") (pintype "passive"))
      (node (ref "F1") (pin "2") (pinfunction "2_2") (pintype "passive"))
      (node (ref "Q1") (pin "D") (pinfunction "D_D") (pintype "passive"))
      (node (ref "Q3") (pin "D") (pinfunction "D_D") (pintype "passive"))
    )
    (net (code "44") (name "VCC{slash}2") (class "Default")
      (node (ref "C1") (pin "1") (pinfunction "1_1") (pintype "passive"))
      (node (ref "C14") (pin "+") (pinfunction "+_+") (pintype "passive"))
      (node (ref "C15") (pin "+") (pinfunction "+_+") (pintype "passive"))
      (node (ref "C18") (pin "1") (pinfunction "1_1") (pintype "passive"))
      (node (ref "C19") (pin "+") (pinfunction "+_+") (pintype "passive"))
      (node (ref "C20") (pin "1") (pinfunction "1_1") (pintype "passive"))
      (node (ref "C9") (pin "1") (pinfunction "1_1") (pintype "passive"))
      (node (ref "CON1") (pin "10") (pinfunction "10_10") (pintype "passive"))
      (node (ref "CON1") (pin "9") (pinfunction "9_9") (pintype "passive"))
      (node (ref "D7") (pin "A") (pinfunction "A_A") (pintype "passive"))
      (node (ref "D8") (pin "A") (pinfunction "A_A") (pintype "passive"))
      (node (ref "IC4") (pin "5") (pinfunction "VCC_5") (pintype "power_in"))
      (node (ref "IC5") (pin "5") (pinfunction "VCC_5") (pintype "power_in"))
      (node (ref "IC6") (pin "3") (pinfunction "VO_3") (pintype "passive"))
      (node (ref "IC7") (pin "1") (pinfunction "VI_1") (pintype "input"))
      (node (ref "J1") (pin "2") (pinfunction "2_2") (pintype "passive"))
    )
    (net (code "45") (name "unconnected-(IC1A-DEMO-Pad10)") (class "Default")
      (node (ref "IC1") (pin "10") (pinfunction "DEMO_10") (pintype "output"))
    )
    (net (code "46") (name "unconnected-(IC1A-PC1-Pad2)") (class "Default")
      (node (ref "IC1") (pin "2") (pinfunction "PC1_2") (pintype "output"))
    )
    (net (code "47") (name "unconnected-(IC1A-PC2-Pad13)") (class "Default")
      (node (ref "IC1") (pin "13") (pinfunction "PC2_13") (pintype "output"))
    )
    (net (code "48") (name "unconnected-(IC1A-PP-Pad1)") (class "Default")
      (node (ref "IC1") (pin "1") (pinfunction "PP_1") (pintype "output"))
    )
    (net (code "49") (name "unconnected-(IC1A-ZEN-Pad15)") (class "Default")
      (node (ref "IC1") (pin "15") (pinfunction "ZEN_15") (pintype "input"))
    )
  )
)
